# 08_DC_DC.net
KiCad netlist of a schematic drawn in Altium Designer
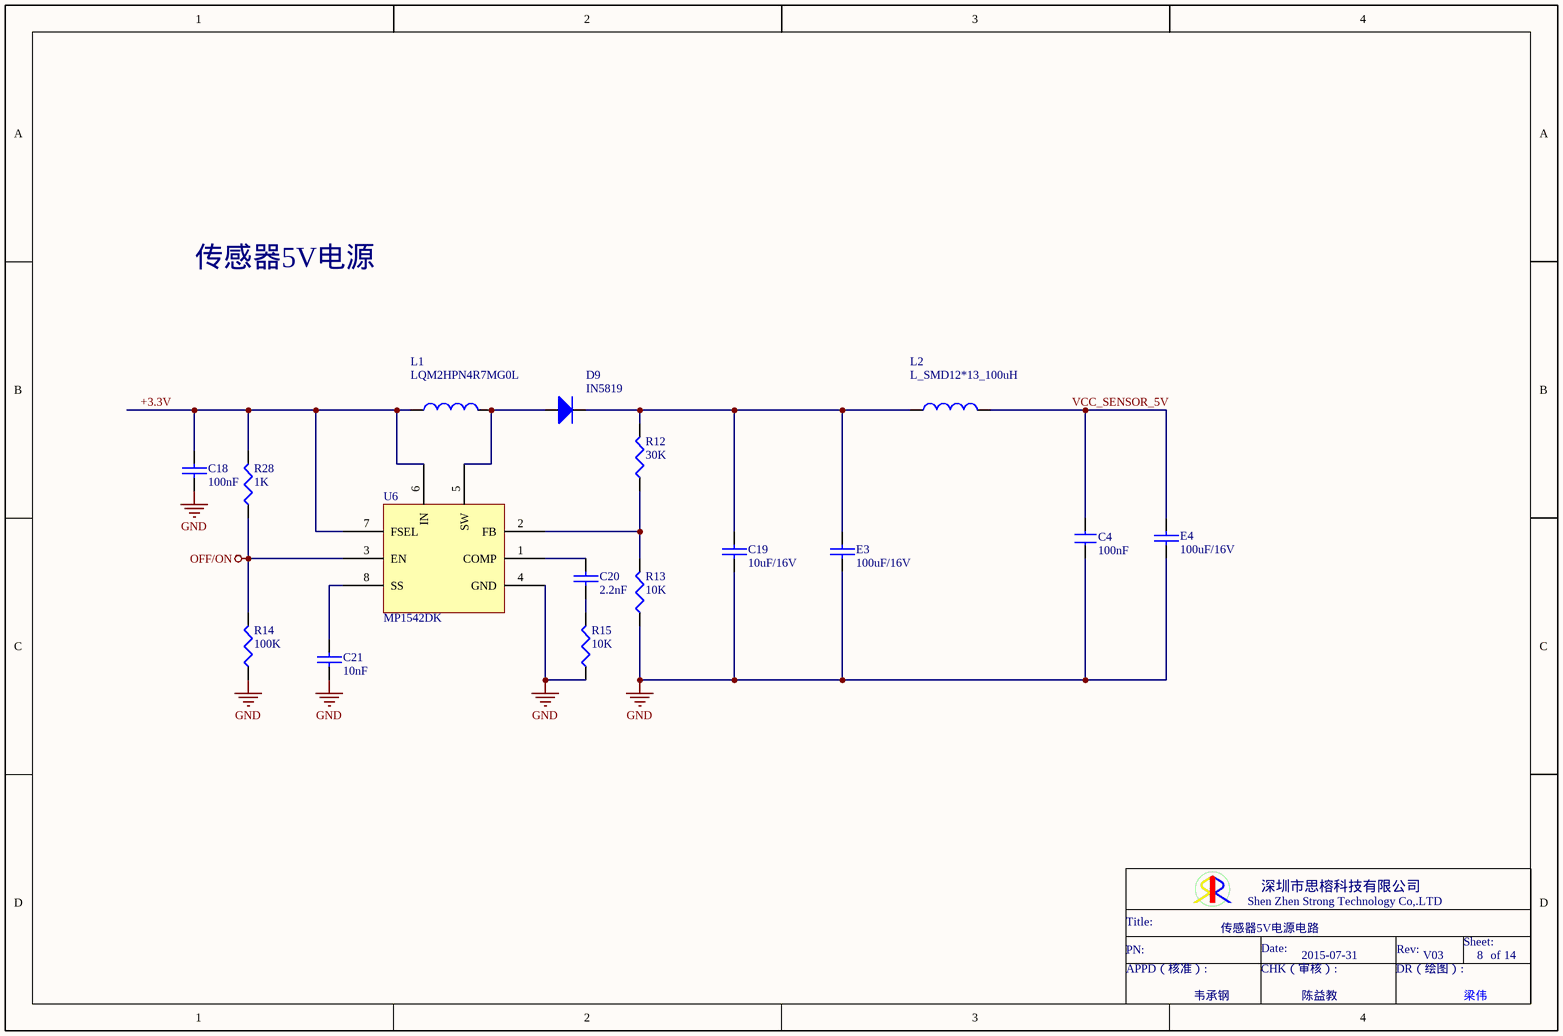
[diagram p0: 08_DC_DC.SchDoc]

(export (version "E")
  (design (tool "Eeschema 10.0.6"))
  (components
    (comp (ref "C4")
      (value "100nF")
      (footprint "0603C")
      (description "Capacitor")
      (libsource (lib "*") (part "电容"))
    )
    (comp (ref "C18")
      (value "100nF")
      (footprint "0603C")
      (description "Capacitor")
      (libsource (lib "Mylibrary") (part "CAP"))
    )
    (comp (ref "C19")
      (value "10uF/16V")
      (footprint "A")
      (description "Capacitor")
      (libsource (lib "Mylibrary") (part "CAP"))
    )
    (comp (ref "C20")
      (value "2.2nF")
      (footprint "0603C")
      (description "Capacitor")
      (libsource (lib "Mylibrary") (part "CAP"))
    )
    (comp (ref "C21")
      (value "10nF")
      (footprint "0603C")
      (description "Capacitor")
      (libsource (lib "Mylibrary") (part "CAP"))
    )
    (comp (ref "D9")
      (value "IN5819")
      (footprint "1206D")
      (description "二极管")
      (libsource (lib "Mylibrary") (part "D"))
    )
    (comp (ref "E3")
      (value "100uF/16V")
      (footprint "6032")
      (description "Capacitor")
      (libsource (lib "Mylibrary") (part "CAP"))
    )
    (comp (ref "E4")
      (value "100uF/16V")
      (footprint "6032")
      (description "Capacitor")
      (libsource (lib "Mylibrary") (part "CAP"))
    )
    (comp (ref "L1")
      (value "LQM2HPN4R7MG0L")
      (footprint "3225")
      (description "Inductor")
      (fields (field (name "PUBLISHER") "Altium Limited"))
      (libsource (lib "Miscellaneous Devices") (part "Inductor"))
    )
    (comp (ref "L2")
      (value "L_SMD12*13_100uH")
      (footprint "L-SMD12*13")
      (description "Inductor")
      (fields (field (name "PUBLISHER") "Altium Limited"))
      (libsource (lib "Miscellaneous Devices") (part "Inductor"))
    )
    (comp (ref "R12") (value "30K") (footprint "0603R") (libsource (lib "Mylibrary") (part "RES1")))
    (comp (ref "R13") (value "10K") (footprint "0603R") (libsource (lib "Mylibrary") (part "RES1")))
    (comp (ref "R14") (value "100K") (footprint "0603R") (libsource (lib "Mylibrary") (part "RES1")))
    (comp (ref "R15") (value "10K") (footprint "0603R") (libsource (lib "Mylibrary") (part "RES1")))
    (comp (ref "R28") (value "1K") (footprint "0603R") (libsource (lib "Mylibrary") (part "RES1")))
    (comp (ref "U6")
      (value "MP1542DK")
      (footprint "SSOP8")
      (description "MPS公司产品   DC-DC控制IC")
      (fields (field (name "PUBLISHER") "Altium Limited"))
      (libsource (lib "Mylibrary") (part "MP1542DK"))
    )
  )
  (nets
    (net (code "1") (name "/+3.3V") (class "Default")
      (node (ref "C18") (pin "1") (pinfunction "1_1") (pintype "passive"))
      (node (ref "L1") (pin "1") (pinfunction "1_1") (pintype "passive"))
      (node (ref "R28") (pin "2") (pinfunction "2_2") (pintype "passive"))
      (node (ref "U6") (pin "6") (pinfunction "IN_6") (pintype "passive"))
      (node (ref "U6") (pin "7") (pinfunction "FSEL_7") (pintype "passive"))
    )
    (net (code "2") (name "/VCC_SENSOR_5V") (class "Default")
      (node (ref "C4") (pin "1") (pinfunction "1_1") (pintype "passive"))
      (node (ref "E4") (pin "1") (pinfunction "1_1") (pintype "passive"))
      (node (ref "L2") (pin "2") (pinfunction "2_2") (pintype "passive"))
    )
    (net (code "3") (name "GND") (class "Default")
      (node (ref "C18") (pin "2") (pinfunction "2_2") (pintype "passive"))
      (node (ref "C19") (pin "2") (pinfunction "2_2") (pintype "passive"))
      (node (ref "C21") (pin "2") (pinfunction "2_2") (pintype "passive"))
      (node (ref "C4") (pin "2") (pinfunction "2_2") (pintype "passive"))
      (node (ref "E3") (pin "2") (pinfunction "2_2") (pintype "passive"))
      (node (ref "E4") (pin "2") (pinfunction "2_2") (pintype "passive"))
      (node (ref "R13") (pin "1") (pinfunction "1_1") (pintype "passive"))
      (node (ref "R14") (pin "1") (pinfunction "1_1") (pintype "passive"))
      (node (ref "R15") (pin "1") (pinfunction "1_1") (pintype "passive"))
      (node (ref "U6") (pin "4") (pinfunction "GND_4") (pintype "passive"))
    )
    (net (code "4") (name "Net-(C19-Pad1)") (class "Default")
      (node (ref "C19") (pin "1") (pinfunction "1_1") (pintype "passive"))
      (node (ref "D9") (pin "2") (pinfunction "2_2") (pintype "passive"))
      (node (ref "E3") (pin "1") (pinfunction "1_1") (pintype "passive"))
      (node (ref "L2") (pin "1") (pinfunction "1_1") (pintype "passive"))
      (node (ref "R12") (pin "2") (pinfunction "2_2") (pintype "passive"))
    )
    (net (code "5") (name "Net-(C20-Pad2)") (class "Default")
      (node (ref "C20") (pin "2") (pinfunction "2_2") (pintype "passive"))
      (node (ref "R15") (pin "2") (pinfunction "2_2") (pintype "passive"))
    )
    (net (code "6") (name "Net-(U6-COMP)") (class "Default")
      (node (ref "C20") (pin "1") (pinfunction "1_1") (pintype "passive"))
      (node (ref "U6") (pin "1") (pinfunction "COMP_1") (pintype "passive"))
    )
    (net (code "7") (name "Net-(U6-FB)") (class "Default")
      (node (ref "R12") (pin "1") (pinfunction "1_1") (pintype "passive"))
      (node (ref "R13") (pin "2") (pinfunction "2_2") (pintype "passive"))
      (node (ref "U6") (pin "2") (pinfunction "FB_2") (pintype "passive"))
    )
    (net (code "8") (name "Net-(U6-SS)") (class "Default")
      (node (ref "C21") (pin "1") (pinfunction "1_1") (pintype "passive"))
      (node (ref "U6") (pin "8") (pinfunction "SS_8") (pintype "passive"))
    )
    (net (code "9") (name "Net-(U6-SW)") (class "Default")
      (node (ref "D9") (pin "1") (pinfunction "1_1") (pintype "passive"))
      (node (ref "L1") (pin "2") (pinfunction "2_2") (pintype "passive"))
      (node (ref "U6") (pin "5") (pinfunction "SW_5") (pintype "passive"))
    )
    (net (code "10") (name "OFF{slash}ON") (class "Default")
      (node (ref "R14") (pin "2") (pinfunction "2_2") (pintype "passive"))
      (node (ref "R28") (pin "1") (pinfunction "1_1") (pintype "passive"))
      (node (ref "U6") (pin "3") (pinfunction "EN_3") (pintype "passive"))
    )
  )
)
